# sp_esquematico.net
KiCad netlist of a schematic drawn in EAGLE
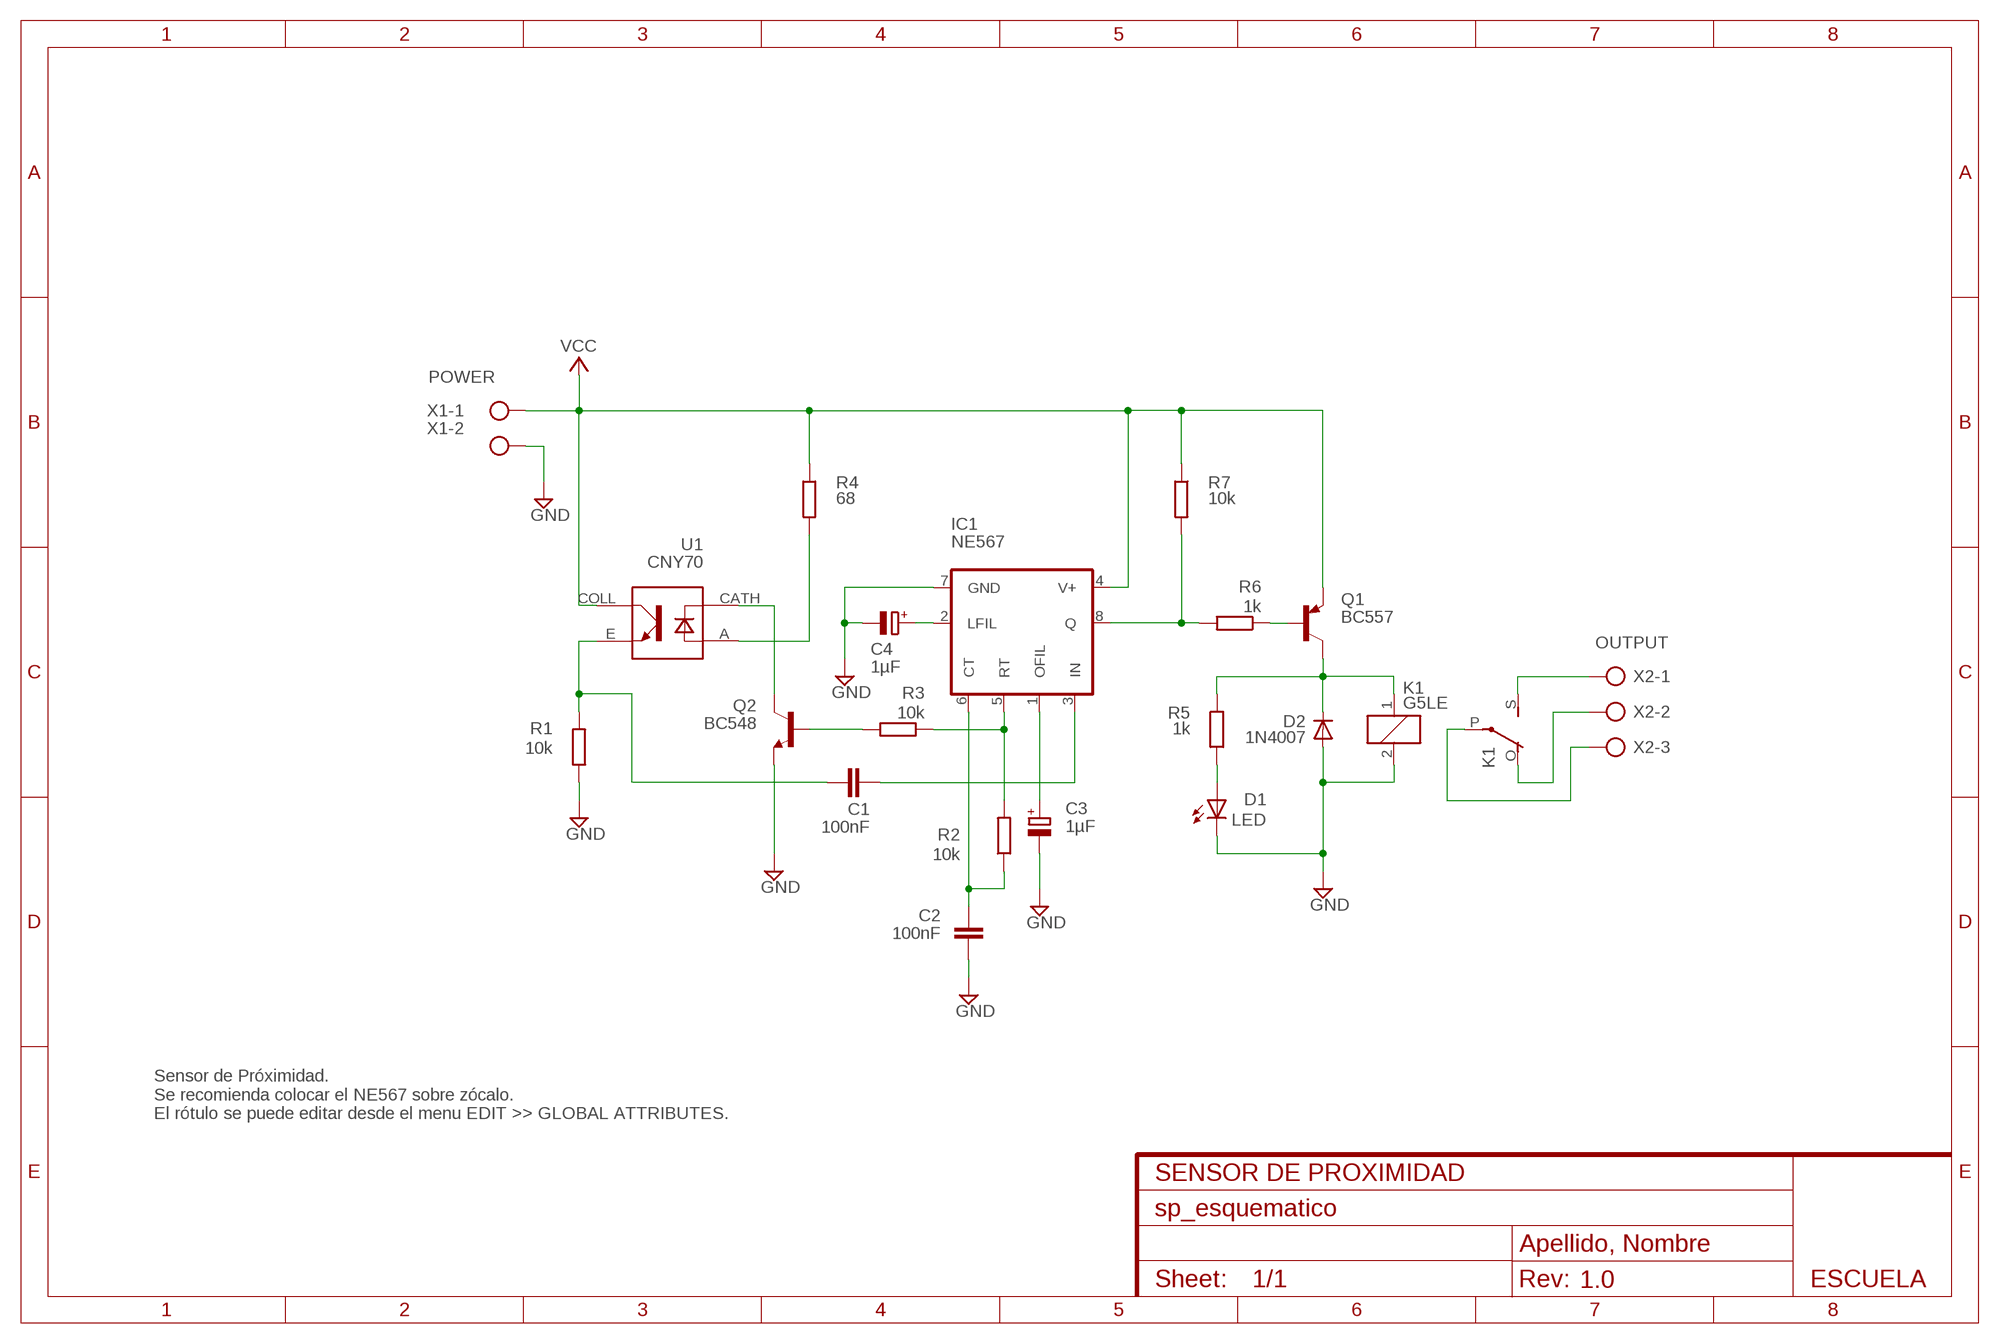
[diagram p0: schematic, sheet 1]

(export (version "E")
  (design (tool "Eeschema 10.0.6"))
  (components
    (comp (ref "C1")
      (value "100nF")
      (footprint "eagle-import:C025-025X050")
      (libsource (lib "eagle-import") (part "C-EU025-025X050"))
    )
    (comp (ref "C2")
      (value "100nF")
      (footprint "eagle-import:C025-025X050")
      (libsource (lib "eagle-import") (part "C-EU025-025X050"))
    )
    (comp (ref "C3")
      (value "1µF")
      (footprint "eagle-import:E2,5-6")
      (libsource (lib "eagle-import") (part "CPOL-EUE2.5-6"))
    )
    (comp (ref "C4")
      (value "1µF")
      (footprint "eagle-import:E2,5-6")
      (libsource (lib "eagle-import") (part "CPOL-EUE2.5-6"))
    )
    (comp (ref "D1")
      (value "LED")
      (footprint "eagle-import:LED_3MM")
      (libsource (lib "eagle-import") (part "LED3MM"))
    )
    (comp (ref "D2")
      (value "1N4007")
      (footprint "eagle-import:DO41-10")
      (libsource (lib "eagle-import") (part "1N4007"))
    )
    (comp (ref "IC1")
      (value "NE567")
      (footprint "eagle-import:DIL08")
      (libsource (lib "eagle-import") (part "NE567NNE"))
    )
    (comp (ref "K1")
      (value "G5LE")
      (footprint "eagle-import:G5LE")
      (libsource (lib "eagle-import") (part "RELE_G5LE"))
    )
    (comp (ref "Q1")
      (value "BC557")
      (footprint "eagle-import:TO92-EBC")
      (libsource (lib "eagle-import") (part "BC557"))
    )
    (comp (ref "Q2")
      (value "BC548")
      (footprint "eagle-import:TO92-EBC")
      (libsource (lib "eagle-import") (part "BC548"))
    )
    (comp (ref "R1")
      (value "10k")
      (footprint "eagle-import:0204_7")
      (libsource (lib "eagle-import") (part "RESISTOR-EU0204/7"))
    )
    (comp (ref "R2")
      (value "10k")
      (footprint "eagle-import:0204_7")
      (libsource (lib "eagle-import") (part "RESISTOR-EU0204/7"))
    )
    (comp (ref "R3")
      (value "10k")
      (footprint "eagle-import:0204_7")
      (libsource (lib "eagle-import") (part "RESISTOR-EU0204/7"))
    )
    (comp (ref "R4")
      (value "68")
      (footprint "eagle-import:0204_7")
      (libsource (lib "eagle-import") (part "RESISTOR-EU0204/7"))
    )
    (comp (ref "R5")
      (value "1k")
      (footprint "eagle-import:0204_7")
      (libsource (lib "eagle-import") (part "RESISTOR-EU0204/7"))
    )
    (comp (ref "R6")
      (value "1k")
      (footprint "eagle-import:0204_7")
      (libsource (lib "eagle-import") (part "RESISTOR-EU0204/7"))
    )
    (comp (ref "R7")
      (value "10k")
      (footprint "eagle-import:0204_7")
      (libsource (lib "eagle-import") (part "RESISTOR-EU0204/7"))
    )
    (comp (ref "U1")
      (value "CNY70")
      (footprint "eagle-import:DIPS254W50P254L710H600Q4")
      (fields (field (name "MF") "Vishay"))
      (libsource (lib "eagle-import") (part "CNY70"))
    )
    (comp (ref "X1")
      (value "POWER")
      (footprint "eagle-import:AK500_2")
      (libsource (lib "eagle-import") (part "BORNERA_AK500/2"))
    )
    (comp (ref "X2")
      (value "OUTPUT")
      (footprint "eagle-import:AK500_3")
      (libsource (lib "eagle-import") (part "BORNERA_AK500/3"))
    )
  )
  (nets
    (net (code "1") (name "GND") (class "Default")
      (node (ref "C2") (pin "2") (pinfunction "2_2") (pintype "passive"))
      (node (ref "C3") (pin "-") (pinfunction "-_-") (pintype "passive"))
      (node (ref "C4") (pin "-") (pinfunction "-_-") (pintype "passive"))
      (node (ref "D1") (pin "K") (pinfunction "C_K") (pintype "passive"))
      (node (ref "D2") (pin "A") (pinfunction "A_A") (pintype "passive"))
      (node (ref "IC1") (pin "7") (pinfunction "GND_7") (pintype "power_in"))
      (node (ref "K1") (pin "2") (pinfunction "2_2") (pintype "passive"))
      (node (ref "Q2") (pin "E") (pinfunction "E_E") (pintype "passive"))
      (node (ref "R1") (pin "1") (pinfunction "1_1") (pintype "passive"))
      (node (ref "X1") (pin "2") (pinfunction "KL_2") (pintype "passive"))
    )
    (net (code "2") (name "Net-(C1-Pad1)") (class "Default")
      (node (ref "C1") (pin "1") (pinfunction "1_1") (pintype "passive"))
      (node (ref "R1") (pin "2") (pinfunction "2_2") (pintype "passive"))
      (node (ref "U1") (pin "E") (pinfunction "E_E") (pintype "passive"))
    )
    (net (code "3") (name "Net-(D1-PadA)") (class "Default")
      (node (ref "D1") (pin "A") (pinfunction "A_A") (pintype "passive"))
      (node (ref "R5") (pin "2") (pinfunction "2_2") (pintype "passive"))
    )
    (net (code "4") (name "Net-(D2-PadC)") (class "Default")
      (node (ref "D2") (pin "C") (pinfunction "C_C") (pintype "passive"))
      (node (ref "K1") (pin "1") (pinfunction "1_1") (pintype "passive"))
      (node (ref "Q1") (pin "C") (pinfunction "C_C") (pintype "passive"))
      (node (ref "R5") (pin "1") (pinfunction "1_1") (pintype "passive"))
    )
    (net (code "5") (name "Net-(IC1-CT)") (class "Default")
      (node (ref "C2") (pin "1") (pinfunction "1_1") (pintype "passive"))
      (node (ref "IC1") (pin "6") (pinfunction "CT_6") (pintype "passive"))
      (node (ref "R2") (pin "1") (pinfunction "1_1") (pintype "passive"))
    )
    (net (code "6") (name "Net-(IC1-IN)") (class "Default")
      (node (ref "C1") (pin "2") (pinfunction "2_2") (pintype "passive"))
      (node (ref "IC1") (pin "3") (pinfunction "IN_3") (pintype "input"))
    )
    (net (code "7") (name "Net-(IC1-LFIL)") (class "Default")
      (node (ref "C4") (pin "+") (pinfunction "+_+") (pintype "passive"))
      (node (ref "IC1") (pin "2") (pinfunction "LFIL_2") (pintype "passive"))
    )
    (net (code "8") (name "Net-(IC1-OFIL)") (class "Default")
      (node (ref "C3") (pin "+") (pinfunction "+_+") (pintype "passive"))
      (node (ref "IC1") (pin "1") (pinfunction "OFIL_1") (pintype "output"))
    )
    (net (code "9") (name "Net-(IC1-Q)") (class "Default")
      (node (ref "IC1") (pin "8") (pinfunction "Q_8") (pintype "output"))
      (node (ref "R6") (pin "2") (pinfunction "2_2") (pintype "passive"))
      (node (ref "R7") (pin "2") (pinfunction "2_2") (pintype "passive"))
    )
    (net (code "10") (name "Net-(IC1-RT)") (class "Default")
      (node (ref "IC1") (pin "5") (pinfunction "RT_5") (pintype "passive"))
      (node (ref "R2") (pin "2") (pinfunction "2_2") (pintype "passive"))
      (node (ref "R3") (pin "1") (pinfunction "1_1") (pintype "passive"))
    )
    (net (code "11") (name "Net-(K1B-COM)") (class "Default")
      (node (ref "K1") (pin "P") (pinfunction "COM_P") (pintype "passive"))
      (node (ref "X2") (pin "3") (pinfunction "KL_3") (pintype "passive"))
    )
    (net (code "12") (name "Net-(K1B-NA)") (class "Default")
      (node (ref "K1") (pin "S") (pinfunction "NA_S") (pintype "passive"))
      (node (ref "X2") (pin "1") (pinfunction "KL_1") (pintype "passive"))
    )
    (net (code "13") (name "Net-(K1B-NC)") (class "Default")
      (node (ref "K1") (pin "O") (pinfunction "NC_O") (pintype "passive"))
      (node (ref "X2") (pin "2") (pinfunction "KL_2") (pintype "passive"))
    )
    (net (code "14") (name "Net-(Q1-PadB)") (class "Default")
      (node (ref "Q1") (pin "B") (pinfunction "B_B") (pintype "passive"))
      (node (ref "R6") (pin "1") (pinfunction "1_1") (pintype "passive"))
    )
    (net (code "15") (name "Net-(Q2-PadB)") (class "Default")
      (node (ref "Q2") (pin "B") (pinfunction "B_B") (pintype "passive"))
      (node (ref "R3") (pin "2") (pinfunction "2_2") (pintype "passive"))
    )
    (net (code "16") (name "Net-(Q2-PadC)") (class "Default")
      (node (ref "Q2") (pin "C") (pinfunction "C_C") (pintype "passive"))
      (node (ref "U1") (pin "CATH") (pinfunction "CATH_CATH") (pintype "passive"))
    )
    (net (code "17") (name "Net-(R4-Pad2)") (class "Default")
      (node (ref "R4") (pin "2") (pinfunction "2_2") (pintype "passive"))
      (node (ref "U1") (pin "A") (pinfunction "A_A") (pintype "passive"))
    )
    (net (code "18") (name "VCC") (class "Default")
      (node (ref "IC1") (pin "4") (pinfunction "V+_4") (pintype "power_in"))
      (node (ref "Q1") (pin "E") (pinfunction "E_E") (pintype "passive"))
      (node (ref "R4") (pin "1") (pinfunction "1_1") (pintype "passive"))
      (node (ref "R7") (pin "1") (pinfunction "1_1") (pintype "passive"))
      (node (ref "U1") (pin "COLL") (pinfunction "COLL_COLL") (pintype "passive"))
      (node (ref "X1") (pin "1") (pinfunction "KL_1") (pintype "passive"))
    )
  )
)
